# Motor_Control.net
KiCad netlist of a schematic drawn in Altium Designer
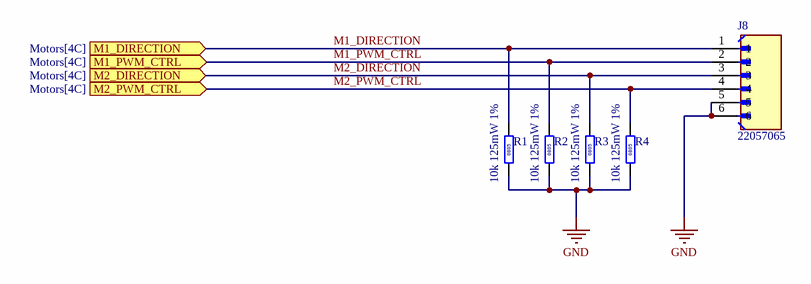
[diagram p0: Motor_Control.SchDoc]

(export (version "E")
  (design (tool "Eeschema 10.0.6"))
  (components
    (comp (ref "J8")
      (value "22057065")
      (footprint "MOLEX_22057065")
      (description "Conn Shrouded Header (4 Sides) HDR 6 POS 2.5mm Solder RA Side Entry Thru-Hole SPOXâ„¢ Bag")
      (fields (field (name "MF") "Molex"))
      (libsource (lib "22057065") (part "22057065"))
    )
    (comp (ref "R1")
      (value "10k 125mW 1%")
      (footprint "RESC2013X60X35ML10T20")
      (description "Res, SMD, 10k, 125mW, 1%, ±200ppm, 0805")
      (fields
        (field (name "MANUFACTURER") "Panasonic")
        (field (name "MANUFACTURERPARTNUMBER") "ERJ-6GEYJ103V")
      )
      (libsource (lib "Andor Technology") (part "Resistor_0805"))
    )
    (comp (ref "R2")
      (value "10k 125mW 1%")
      (footprint "RESC2013X60X35ML10T20")
      (description "Res, SMD, 10k, 125mW, 1%, ±200ppm, 0805")
      (fields
        (field (name "MANUFACTURER") "Panasonic")
        (field (name "MANUFACTURERPARTNUMBER") "ERJ-6GEYJ103V")
      )
      (libsource (lib "Andor Technology") (part "Resistor_0805"))
    )
    (comp (ref "R3")
      (value "10k 125mW 1%")
      (footprint "RESC2013X60X35ML10T20")
      (description "Res, SMD, 10k, 125mW, 1%, ±200ppm, 0805")
      (fields
        (field (name "MANUFACTURER") "Panasonic")
        (field (name "MANUFACTURERPARTNUMBER") "ERJ-6GEYJ103V")
      )
      (libsource (lib "Andor Technology") (part "Resistor_0805"))
    )
    (comp (ref "R4")
      (value "10k 125mW 1%")
      (footprint "RESC2013X60X35ML10T20")
      (description "Res, SMD, 10k, 125mW, 1%, ±200ppm, 0805")
      (fields
        (field (name "MANUFACTURER") "Panasonic")
        (field (name "MANUFACTURERPARTNUMBER") "ERJ-6GEYJ103V")
      )
      (libsource (lib "Andor Technology") (part "Resistor_0805"))
    )
  )
  (nets
    (net (code "1") (name "/M1_DIRECTION") (class "Default")
      (node (ref "J8") (pin "1") (pinfunction "1_1") (pintype "passive"))
      (node (ref "R1") (pin "2") (pinfunction "2_2") (pintype "passive"))
    )
    (net (code "2") (name "/M1_PWM_CTRL") (class "Default")
      (node (ref "J8") (pin "2") (pinfunction "2_2") (pintype "passive"))
      (node (ref "R2") (pin "2") (pinfunction "2_2") (pintype "passive"))
    )
    (net (code "3") (name "/M2_DIRECTION") (class "Default")
      (node (ref "J8") (pin "3") (pinfunction "3_3") (pintype "passive"))
      (node (ref "R3") (pin "2") (pinfunction "2_2") (pintype "passive"))
    )
    (net (code "4") (name "/M2_PWM_CTRL") (class "Default")
      (node (ref "J8") (pin "4") (pinfunction "4_4") (pintype "passive"))
      (node (ref "R4") (pin "2") (pinfunction "2_2") (pintype "passive"))
    )
    (net (code "5") (name "GND") (class "Default")
      (node (ref "J8") (pin "5") (pinfunction "5_5") (pintype "passive"))
      (node (ref "J8") (pin "6") (pinfunction "6_6") (pintype "passive"))
      (node (ref "R1") (pin "1") (pinfunction "1_1") (pintype "passive"))
      (node (ref "R2") (pin "1") (pinfunction "1_1") (pintype "passive"))
      (node (ref "R3") (pin "1") (pinfunction "1_1") (pintype "passive"))
      (node (ref "R4") (pin "1") (pinfunction "1_1") (pintype "passive"))
    )
  )
)
